# INPUT_OUTPUT.net
KiCad netlist of a schematic drawn in Altium Designer
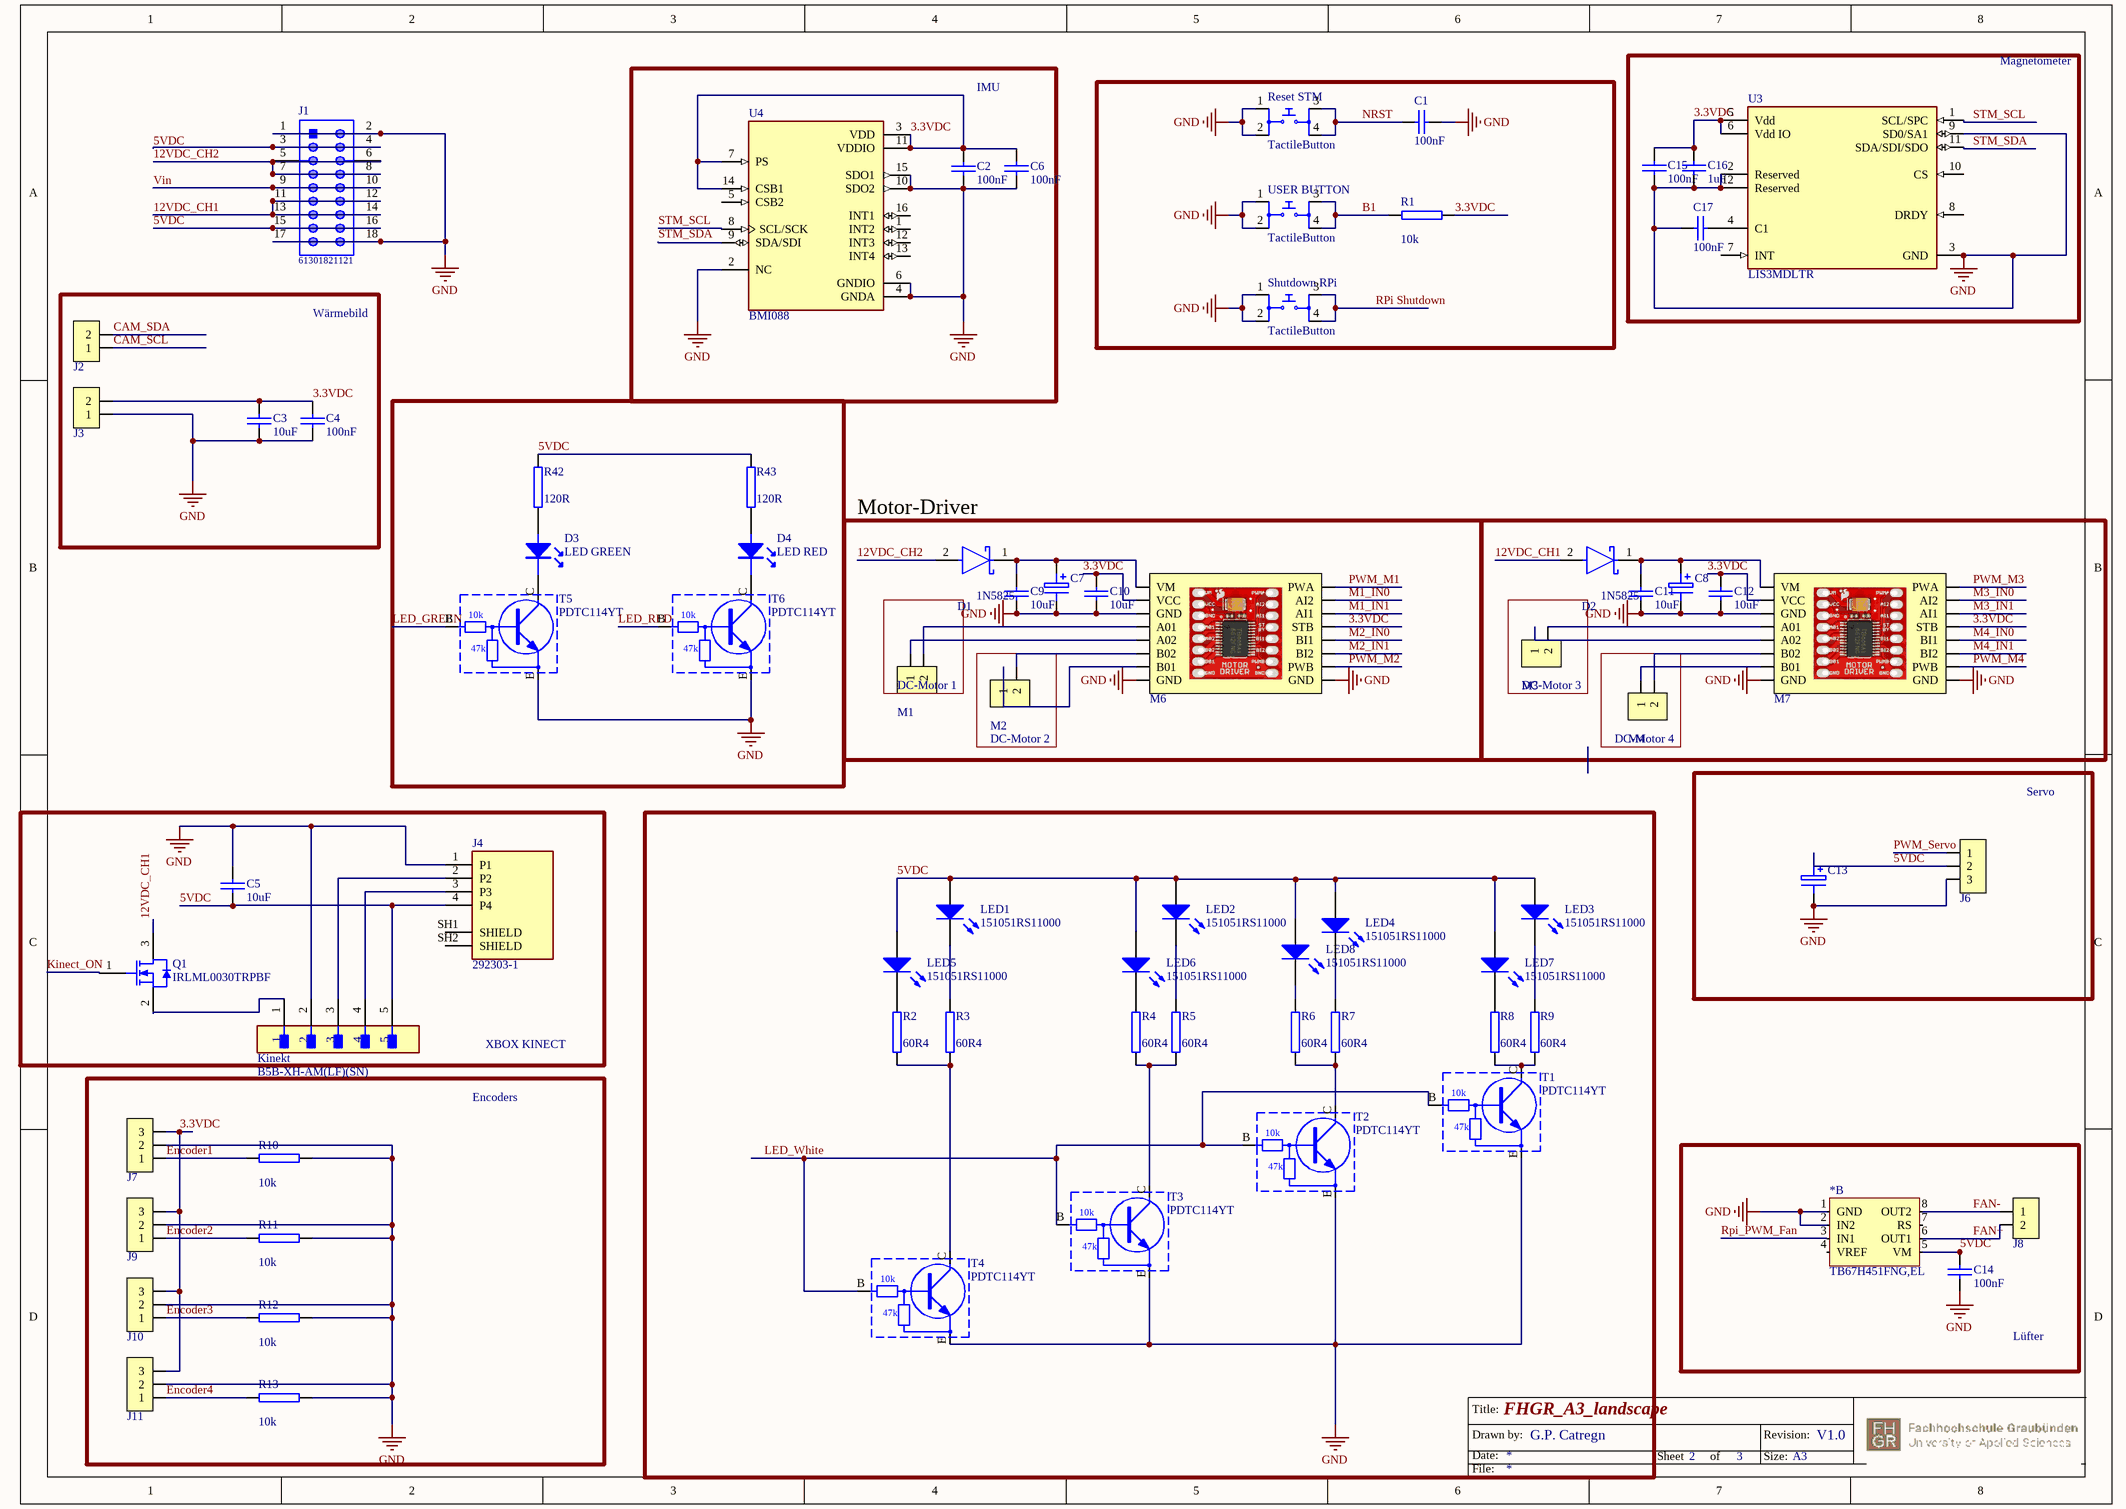
[diagram p0: INPUT_OUTPUT.SchDoc]

(export (version "E")
  (design (tool "Eeschema 10.0.6"))
  (components
    (comp (ref "*")
      (value "TB67H451FNG,EL")
      (footprint "SOIC127P600X170_HS-9N")
      (libsource (lib "TB67H451FNG,EL") (part "TB67H451FNG,EL"))
    )
    (comp (ref "C1")
      (value "100nF")
      (footprint "0603")
      (fields
        (field (name "TOLERANCE") "-20%/+80%")
        (field (name "VOLTAGE") "50V")
        (field (name "Comment") "C 100nF 0603")
      )
      (libsource (lib "FHGR_Altium_database") (part "Capacitor"))
    )
    (comp (ref "C2")
      (value "100nF")
      (footprint "0603")
      (fields
        (field (name "TOLERANCE") "-20%/+80%")
        (field (name "VOLTAGE") "50V")
        (field (name "Comment") "C 100nF 0603")
      )
      (libsource (lib "FHGR_Altium_database") (part "Capacitor"))
    )
    (comp (ref "C3")
      (value "10uF")
      (footprint "0603")
      (fields
        (field (name "TOLERANCE") "10%")
        (field (name "VOLTAGE") "16V")
        (field (name "Comment") "C 10uF 0603")
      )
      (libsource (lib "FHGR_Altium_database") (part "Capacitor"))
    )
    (comp (ref "C4")
      (value "100nF")
      (footprint "0603")
      (fields
        (field (name "TOLERANCE") "-20%/+80%")
        (field (name "VOLTAGE") "50V")
        (field (name "Comment") "C 100nF 0603")
      )
      (libsource (lib "FHGR_Altium_database") (part "Capacitor"))
    )
    (comp (ref "C5")
      (value "10uF")
      (footprint "0603")
      (fields
        (field (name "TOLERANCE") "10%")
        (field (name "VOLTAGE") "16V")
        (field (name "Comment") "C 10uF 0603")
      )
      (libsource (lib "FHGR_Altium_database") (part "Capacitor"))
    )
    (comp (ref "C6")
      (value "100nF")
      (footprint "0603")
      (fields
        (field (name "TOLERANCE") "-20%/+80%")
        (field (name "VOLTAGE") "50V")
        (field (name "Comment") "C 100nF 0603")
      )
      (libsource (lib "FHGR_Altium_database") (part "Capacitor"))
    )
    (comp (ref "C7")
      (value "C 100uF ALUM")
      (footprint "PCAP_8x10-ELEC00")
      (fields (field (name "TOLERANCE") "20%") (field (name "VOLTAGE") "50V"))
      (libsource (lib "FHGR_Altium_database") (part "Capacitor_Pol"))
    )
    (comp (ref "C8")
      (value "C 100uF ALUM")
      (footprint "PCAP_8x10-ELEC00")
      (fields (field (name "TOLERANCE") "20%") (field (name "VOLTAGE") "50V"))
      (libsource (lib "FHGR_Altium_database") (part "Capacitor_Pol"))
    )
    (comp (ref "C9")
      (value "10uF")
      (footprint "0603")
      (fields
        (field (name "TOLERANCE") "10%")
        (field (name "VOLTAGE") "16V")
        (field (name "Comment") "C 10uF 0603")
      )
      (libsource (lib "FHGR_Altium_database") (part "Capacitor"))
    )
    (comp (ref "C10")
      (value "10uF")
      (footprint "0603")
      (fields
        (field (name "TOLERANCE") "10%")
        (field (name "VOLTAGE") "16V")
        (field (name "Comment") "C 10uF 0603")
      )
      (libsource (lib "FHGR_Altium_database") (part "Capacitor"))
    )
    (comp (ref "C11")
      (value "10uF")
      (footprint "0603")
      (fields
        (field (name "TOLERANCE") "10%")
        (field (name "VOLTAGE") "16V")
        (field (name "Comment") "C 10uF 0603")
      )
      (libsource (lib "FHGR_Altium_database") (part "Capacitor"))
    )
    (comp (ref "C12")
      (value "10uF")
      (footprint "0603")
      (fields
        (field (name "TOLERANCE") "10%")
        (field (name "VOLTAGE") "16V")
        (field (name "Comment") "C 10uF 0603")
      )
      (libsource (lib "FHGR_Altium_database") (part "Capacitor"))
    )
    (comp (ref "C13")
      (value "C 100uF ALUM")
      (footprint "PCAP_8x10-ELEC00")
      (fields (field (name "TOLERANCE") "20%") (field (name "VOLTAGE") "50V"))
      (libsource (lib "FHGR_Altium_database") (part "Capacitor_Pol"))
    )
    (comp (ref "C14")
      (value "100nF")
      (footprint "0603")
      (fields
        (field (name "TOLERANCE") "-20%/+80%")
        (field (name "VOLTAGE") "50V")
        (field (name "Comment") "C 100nF 0603")
      )
      (libsource (lib "FHGR_Altium_database") (part "Capacitor"))
    )
    (comp (ref "C15")
      (value "100nF")
      (footprint "0603")
      (fields
        (field (name "TOLERANCE") "-20%/+80%")
        (field (name "VOLTAGE") "50V")
        (field (name "Comment") "C 100nF 0603")
      )
      (libsource (lib "FHGR_Altium_database") (part "Capacitor"))
    )
    (comp (ref "C16")
      (value "1uF")
      (footprint "0603")
      (fields
        (field (name "TOLERANCE") "10%")
        (field (name "VOLTAGE") "25V")
        (field (name "Comment") "C 1uF 0603")
      )
      (libsource (lib "FHGR_Altium_database") (part "Capacitor"))
    )
    (comp (ref "C17")
      (value "100nF")
      (footprint "0603")
      (fields
        (field (name "TOLERANCE") "-20%/+80%")
        (field (name "VOLTAGE") "50V")
        (field (name "Comment") "C 100nF 0603")
      )
      (libsource (lib "FHGR_Altium_database") (part "Capacitor"))
    )
    (comp (ref "D1")
      (value "1N5825")
      (footprint "Microsemi_1N5825_0")
      (libsource (lib "Diode_Microsemi_1N5825_eec") (part "1N5825"))
    )
    (comp (ref "D2")
      (value "1N5825")
      (footprint "Microsemi_1N5825_0")
      (libsource (lib "Diode_Microsemi_1N5825_eec") (part "1N5825"))
    )
    (comp (ref "D3")
      (value "LED GREEN")
      (footprint "LED_1206")
      (libsource (lib "FHGR_Altium_database") (part "LED"))
    )
    (comp (ref "D4")
      (value "LED RED")
      (footprint "LED_1206")
      (libsource (lib "FHGR_Altium_database") (part "LED"))
    )
    (comp (ref "J1")
      (value "61301821121")
      (footprint "61301821121")
      (description "THT Vertical Pin Header WR-PHD, Pitch 2.54 mm, Dual Row, 18 pins")
      (fields (field (name "MANUFACTURER") "Wurth Elektronik") (field (name "PUBLISHER") "WurthElektronik"))
      (libsource (lib "Altium Content Vault") (part "WE-CN-2P-M-R18"))
    )
    (comp (ref "J2")
      (value "2Pin_Male")
      (footprint "Header1x2_254")
      (libsource (lib "FHGR_Altium_database") (part "Connector2Pin"))
    )
    (comp (ref "J3")
      (value "2Pin_Male")
      (footprint "Header1x2_254")
      (libsource (lib "FHGR_Altium_database") (part "Connector2Pin"))
    )
    (comp (ref "J4")
      (value "292303-1")
      (footprint "TE_292303-1")
      (description "CONN USB RECEPT R/A TYPE A 4POS")
      (libsource (lib "292303-1") (part "292303-1"))
    )
    (comp (ref "J6")
      (value "3Pin_Male")
      (footprint "Header1x3_254")
      (libsource (lib "FHGR_Altium_database") (part "Connector3Pin"))
    )
    (comp (ref "J7")
      (value "3Pin_Male")
      (footprint "Header1x3_254")
      (libsource (lib "") (part "Connector3Pin_1"))
    )
    (comp (ref "J8")
      (value "2Pin_Male")
      (footprint "Header1x2_254")
      (libsource (lib "") (part "Connector2Pin_1"))
    )
    (comp (ref "J9")
      (value "3Pin_Male")
      (footprint "Header1x3_254")
      (libsource (lib "") (part "Connector3Pin_1"))
    )
    (comp (ref "J10")
      (value "3Pin_Male")
      (footprint "Header1x3_254")
      (libsource (lib "") (part "Connector3Pin_1"))
    )
    (comp (ref "J11")
      (value "3Pin_Male")
      (footprint "Header1x3_254")
      (libsource (lib "") (part "Connector3Pin_1"))
    )
    (comp (ref "Kinekt")
      (value "B5B-XH-AM(LF)(SN)")
      (footprint "FP-B5B-XH-AM_LF_SN-MFG")
      (description "CONN HEADER VERT 5POS 2.5MM")
      (libsource (lib "Altium Content Vault") (part "bf93c07fd2649a848d0ec8585582aab"))
    )
    (comp (ref "LED1")
      (value "151051RS11000")
      (footprint "Type 5mm")
      (description "THT LED round mono-color color lens, WL-TMRW, Red")
      (fields (field (name "MANUFACTURER") "Wuerth Elektronik"))
      (libsource (lib "Altium Content Vault") (part "WE-LED_K1A2-2"))
    )
    (comp (ref "LED2")
      (value "151051RS11000")
      (footprint "Type 5mm")
      (description "THT LED round mono-color color lens, WL-TMRW, Red")
      (fields (field (name "MANUFACTURER") "Wuerth Elektronik"))
      (libsource (lib "Altium Content Vault") (part "WE-LED_K1A2-2"))
    )
    (comp (ref "LED3")
      (value "151051RS11000")
      (footprint "Type 5mm")
      (description "THT LED round mono-color color lens, WL-TMRW, Red")
      (fields (field (name "MANUFACTURER") "Wuerth Elektronik"))
      (libsource (lib "Altium Content Vault") (part "WE-LED_K1A2-2"))
    )
    (comp (ref "LED4")
      (value "151051RS11000")
      (footprint "Type 5mm")
      (description "THT LED round mono-color color lens, WL-TMRW, Red")
      (fields (field (name "MANUFACTURER") "Wuerth Elektronik"))
      (libsource (lib "Altium Content Vault") (part "WE-LED_K1A2-2"))
    )
    (comp (ref "LED5")
      (value "151051RS11000")
      (footprint "Type 5mm")
      (description "THT LED round mono-color color lens, WL-TMRW, Red")
      (fields (field (name "MANUFACTURER") "Wuerth Elektronik"))
      (libsource (lib "Altium Content Vault") (part "WE-LED_K1A2-2"))
    )
    (comp (ref "LED6")
      (value "151051RS11000")
      (footprint "Type 5mm")
      (description "THT LED round mono-color color lens, WL-TMRW, Red")
      (fields (field (name "MANUFACTURER") "Wuerth Elektronik"))
      (libsource (lib "Altium Content Vault") (part "WE-LED_K1A2-2"))
    )
    (comp (ref "LED7")
      (value "151051RS11000")
      (footprint "Type 5mm")
      (description "THT LED round mono-color color lens, WL-TMRW, Red")
      (fields (field (name "MANUFACTURER") "Wuerth Elektronik"))
      (libsource (lib "Altium Content Vault") (part "WE-LED_K1A2-2"))
    )
    (comp (ref "LED8")
      (value "151051RS11000")
      (footprint "Type 5mm")
      (description "THT LED round mono-color color lens, WL-TMRW, Red")
      (fields (field (name "MANUFACTURER") "Wuerth Elektronik"))
      (libsource (lib "Altium Content Vault") (part "WE-LED_K1A2-2"))
    )
    (comp (ref "M1")
      (value "2Pin_Female")
      (footprint "OSTTE020104")
      (libsource (lib "FHGR_Altium_database") (part "Connector2Pin"))
    )
    (comp (ref "M2")
      (value "2Pin_Female")
      (footprint "OSTTE020104")
      (libsource (lib "FHGR_Altium_database") (part "Connector2Pin"))
    )
    (comp (ref "M3")
      (value "2Pin_Female")
      (footprint "OSTTE020104")
      (libsource (lib "FHGR_Altium_database") (part "Connector2Pin"))
    )
    (comp (ref "M4")
      (value "2Pin_Female")
      (footprint "OSTTE020104")
      (libsource (lib "FHGR_Altium_database") (part "Connector2Pin"))
    )
    (comp (ref "M6")
      (value "SPARKFUN_ROB_14451")
      (footprint "SPARKFUN_ROB_14451")
      (description "Dual Motor Driver")
      (libsource (lib "FHGR_Altium_database") (part "SPARKFUN_ROB_14451"))
    )
    (comp (ref "M7")
      (value "SPARKFUN_ROB_14451")
      (footprint "SPARKFUN_ROB_14451")
      (description "Dual Motor Driver")
      (libsource (lib "FHGR_Altium_database") (part "SPARKFUN_ROB_14451"))
    )
    (comp (ref "Q1")
      (value "IRLML0030TRPBF")
      (footprint "INTR-SOT-23-3_V")
      (description "HEXFET(R) Power MOSFET, 1.3 W, 4.4 ns, -55 to 150 degC, 3-Pin SOT-23, RoHS, Tape and Reel")
      (fields (field (name "MANUFACTURER") "International Rectifier"))
      (libsource (lib "Altium Content Vault") (part "NEMOS-GSD-3"))
    )
    (comp (ref "R1")
      (value "10k")
      (footprint "0805")
      (fields (field (name "TOLERANCE") "1%") (field (name "Comment") "R 10K 0805"))
      (libsource (lib "FHGR_Altium_database") (part "Resistor"))
    )
    (comp (ref "R2")
      (value "60R4")
      (footprint "0805")
      (fields (field (name "TOLERANCE") "1%") (field (name "Comment") "R 60R4 0805"))
      (libsource (lib "FHGR_Altium_database") (part "Resistor"))
    )
    (comp (ref "R3")
      (value "60R4")
      (footprint "0805")
      (fields (field (name "TOLERANCE") "1%") (field (name "Comment") "R 60R4 0805"))
      (libsource (lib "FHGR_Altium_database") (part "Resistor"))
    )
    (comp (ref "R4")
      (value "60R4")
      (footprint "0805")
      (fields (field (name "TOLERANCE") "1%") (field (name "Comment") "R 60R4 0805"))
      (libsource (lib "FHGR_Altium_database") (part "Resistor"))
    )
    (comp (ref "R5")
      (value "60R4")
      (footprint "0805")
      (fields (field (name "TOLERANCE") "1%") (field (name "Comment") "R 60R4 0805"))
      (libsource (lib "FHGR_Altium_database") (part "Resistor"))
    )
    (comp (ref "R6")
      (value "60R4")
      (footprint "0805")
      (fields (field (name "TOLERANCE") "1%") (field (name "Comment") "R 60R4 0805"))
      (libsource (lib "FHGR_Altium_database") (part "Resistor"))
    )
    (comp (ref "R7")
      (value "60R4")
      (footprint "0805")
      (fields (field (name "TOLERANCE") "1%") (field (name "Comment") "R 60R4 0805"))
      (libsource (lib "FHGR_Altium_database") (part "Resistor"))
    )
    (comp (ref "R8")
      (value "60R4")
      (footprint "0805")
      (fields (field (name "TOLERANCE") "1%") (field (name "Comment") "R 60R4 0805"))
      (libsource (lib "FHGR_Altium_database") (part "Resistor"))
    )
    (comp (ref "R9")
      (value "60R4")
      (footprint "0805")
      (fields (field (name "TOLERANCE") "1%") (field (name "Comment") "R 60R4 0805"))
      (libsource (lib "FHGR_Altium_database") (part "Resistor"))
    )
    (comp (ref "R10")
      (value "10k")
      (footprint "0805")
      (fields (field (name "TOLERANCE") "1%") (field (name "Comment") "R 10K 0805"))
      (libsource (lib "FHGR_Altium_database") (part "Resistor"))
    )
    (comp (ref "R11")
      (value "10k")
      (footprint "0805")
      (fields (field (name "TOLERANCE") "1%") (field (name "Comment") "R 10K 0805"))
      (libsource (lib "FHGR_Altium_database") (part "Resistor"))
    )
    (comp (ref "R12")
      (value "10k")
      (footprint "0805")
      (fields (field (name "TOLERANCE") "1%") (field (name "Comment") "R 10K 0805"))
      (libsource (lib "FHGR_Altium_database") (part "Resistor"))
    )
    (comp (ref "R13")
      (value "10k")
      (footprint "0805")
      (fields (field (name "TOLERANCE") "1%") (field (name "Comment") "R 10K 0805"))
      (libsource (lib "FHGR_Altium_database") (part "Resistor"))
    )
    (comp (ref "R42")
      (value "120R")
      (footprint "0805")
      (fields (field (name "TOLERANCE") "1%") (field (name "Comment") "R 120R 0805"))
      (libsource (lib "FHGR_Altium_database") (part "Resistor"))
    )
    (comp (ref "R43")
      (value "120R")
      (footprint "0805")
      (fields (field (name "TOLERANCE") "1%") (field (name "Comment") "R 120R 0805"))
      (libsource (lib "FHGR_Altium_database") (part "Resistor"))
    )
    (comp (ref "Reset STM")
      (value "TactileButton")
      (footprint "TactileButton-6x6mm")
      (fields (field (name "VOLTAGE") "12V"))
      (libsource (lib "FHGR_Altium_database") (part "Switch_Press_Button_4PIN"))
    )
    (comp (ref "Shutdown RPi")
      (value "TactileButton")
      (footprint "TactileButton-6x6mm")
      (fields (field (name "VOLTAGE") "12V"))
      (libsource (lib "FHGR_Altium_database") (part "Switch_Press_Button_4PIN"))
    )
    (comp (ref "T1")
      (value "PDTC114YT")
      (footprint "SOT-23")
      (fields (field (name "VOLTAGE") "50V"))
      (libsource (lib "FHGR_Altium_database") (part "NPN_10k_47k"))
    )
    (comp (ref "T2")
      (value "PDTC114YT")
      (footprint "SOT-23")
      (fields (field (name "VOLTAGE") "50V"))
      (libsource (lib "FHGR_Altium_database") (part "NPN_10k_47k"))
    )
    (comp (ref "T3")
      (value "PDTC114YT")
      (footprint "SOT-23")
      (fields (field (name "VOLTAGE") "50V"))
      (libsource (lib "FHGR_Altium_database") (part "NPN_10k_47k"))
    )
    (comp (ref "T4")
      (value "PDTC114YT")
      (footprint "SOT-23")
      (fields (field (name "VOLTAGE") "50V"))
      (libsource (lib "FHGR_Altium_database") (part "NPN_10k_47k"))
    )
    (comp (ref "T5")
      (value "PDTC114YT")
      (footprint "SOT-23")
      (fields (field (name "VOLTAGE") "50V"))
      (libsource (lib "FHGR_Altium_database") (part "NPN_10k_47k"))
    )
    (comp (ref "T6")
      (value "PDTC114YT")
      (footprint "SOT-23")
      (fields (field (name "VOLTAGE") "50V"))
      (libsource (lib "FHGR_Altium_database") (part "NPN_10k_47k"))
    )
    (comp (ref "U3")
      (value "LIS3MDLTR")
      (footprint "FP-VFLGA-12-8365767-MFG")
      (description "SENSOR MR I2C/SPI 12LGA")
      (fields
        (field (name "OCTOPART") "https://octopart.com/lis3mdltr-stmicroelectronics-29403125")
        (field (name "MANUFACTURER") "STMicroelectronics")
      )
      (libsource (lib "Altium Content Vault") (part "41c0331d4207a07573b21020ef49d7d"))
    )
    (comp (ref "U4")
      (value "BMI088")
      (footprint "PQFN50P450X300X100-16N")
      (libsource (lib "BMI088") (part "BMI088"))
    )
    (comp (ref "USER BUTTON")
      (value "TactileButton")
      (footprint "TactileButton-6x6mm")
      (fields (field (name "VOLTAGE") "12V"))
      (libsource (lib "FHGR_Altium_database") (part "Switch_Press_Button_4PIN"))
    )
  )
  (nets
    (net (code "1") (name "/3.3VDC") (class "Default")
      (node (ref "C10") (pin "1") (pintype "passive"))
      (node (ref "C12") (pin "1") (pintype "passive"))
      (node (ref "C15") (pin "1") (pintype "passive"))
      (node (ref "C16") (pin "1") (pintype "passive"))
      (node (ref "C2") (pin "1") (pintype "passive"))
      (node (ref "C3") (pin "1") (pintype "passive"))
      (node (ref "C4") (pin "1") (pintype "passive"))
      (node (ref "C6") (pin "1") (pintype "passive"))
      (node (ref "J10") (pin "3") (pinfunction "3_3") (pintype "passive"))
      (node (ref "J11") (pin "3") (pinfunction "3_3") (pintype "passive"))
      (node (ref "J3") (pin "2") (pinfunction "2_2") (pintype "passive"))
      (node (ref "J7") (pin "3") (pinfunction "3_3") (pintype "passive"))
      (node (ref "J9") (pin "3") (pinfunction "3_3") (pintype "passive"))
      (node (ref "M6") (pin "13") (pinfunction "STB_13") (pintype "passive"))
      (node (ref "M6") (pin "2") (pinfunction "VCC_2") (pintype "passive"))
      (node (ref "M7") (pin "13") (pinfunction "STB_13") (pintype "passive"))
      (node (ref "M7") (pin "2") (pinfunction "VCC_2") (pintype "passive"))
      (node (ref "R1") (pin "2") (pintype "passive"))
      (node (ref "U3") (pin "5") (pinfunction "Vdd_5") (pintype "power_in"))
      (node (ref "U3") (pin "6") (pinfunction "Vdd_IO_6") (pintype "power_in"))
      (node (ref "U4") (pin "11") (pinfunction "VDDIO_11") (pintype "power_in"))
      (node (ref "U4") (pin "14") (pinfunction "CSB1_14") (pintype "input"))
      (node (ref "U4") (pin "3") (pinfunction "VDD_3") (pintype "power_in"))
      (node (ref "U4") (pin "7") (pinfunction "PS_7") (pintype "input"))
    )
    (net (code "2") (name "/5VDC") (class "Default")
      (node (ref "*") (pin "5") (pinfunction "VM_5") (pintype "input"))
      (node (ref "C13") (pin "1") (pintype "passive"))
      (node (ref "C14") (pin "1") (pintype "passive"))
      (node (ref "C5") (pin "2") (pintype "passive"))
      (node (ref "J1") (pin "15") (pinfunction "15_15") (pintype "passive"))
      (node (ref "J1") (pin "16") (pinfunction "16_16") (pintype "passive"))
      (node (ref "J1") (pin "3") (pinfunction "3_3") (pintype "passive"))
      (node (ref "J1") (pin "4") (pinfunction "4_4") (pintype "passive"))
      (node (ref "J4") (pin "4") (pinfunction "P4_4") (pintype "passive"))
      (node (ref "J6") (pin "2") (pinfunction "2_2") (pintype "passive"))
      (node (ref "Kinekt") (pin "5") (pinfunction "5_5") (pintype "passive"))
      (node (ref "LED1") (pin "2") (pinfunction "A_2") (pintype "passive"))
      (node (ref "LED2") (pin "2") (pinfunction "A_2") (pintype "passive"))
      (node (ref "LED3") (pin "2") (pinfunction "A_2") (pintype "passive"))
      (node (ref "LED4") (pin "2") (pinfunction "A_2") (pintype "passive"))
      (node (ref "LED5") (pin "2") (pinfunction "A_2") (pintype "passive"))
      (node (ref "LED6") (pin "2") (pinfunction "A_2") (pintype "passive"))
      (node (ref "LED7") (pin "2") (pinfunction "A_2") (pintype "passive"))
      (node (ref "LED8") (pin "2") (pinfunction "A_2") (pintype "passive"))
      (node (ref "R42") (pin "2") (pintype "passive"))
      (node (ref "R43") (pin "2") (pintype "passive"))
    )
    (net (code "3") (name "/12VDC_CH1") (class "Default")
      (node (ref "D2") (pin "2") (pinfunction "A_2") (pintype "passive"))
      (node (ref "J1") (pin "11") (pinfunction "11_11") (pintype "passive"))
      (node (ref "J1") (pin "12") (pinfunction "12_12") (pintype "passive"))
      (node (ref "J1") (pin "13") (pinfunction "13_13") (pintype "passive"))
      (node (ref "J1") (pin "14") (pinfunction "14_14") (pintype "passive"))
      (node (ref "Q1") (pin "3") (pinfunction "D_3") (pintype "passive"))
    )
    (net (code "4") (name "/12VDC_CH2") (class "Default")
      (node (ref "D1") (pin "2") (pinfunction "A_2") (pintype "passive"))
      (node (ref "J1") (pin "5") (pinfunction "5_5") (pintype "passive"))
      (node (ref "J1") (pin "6") (pinfunction "6_6") (pintype "passive"))
      (node (ref "J1") (pin "7") (pinfunction "7_7") (pintype "passive"))
      (node (ref "J1") (pin "8") (pinfunction "8_8") (pintype "passive"))
    )
    (net (code "5") (name "/B1") (class "Default")
      (node (ref "R1") (pin "1") (pintype "passive"))
      (node (ref "USER BUTTON") (pin "3") (pintype "passive"))
      (node (ref "USER BUTTON") (pin "4") (pintype "passive"))
    )
    (net (code "6") (name "/CAM_SCL") (class "Default")
      (node (ref "J2") (pin "1") (pinfunction "1_1") (pintype "passive"))
    )
    (net (code "7") (name "/CAM_SDA") (class "Default")
      (node (ref "J2") (pin "2") (pinfunction "2_2") (pintype "passive"))
    )
    (net (code "8") (name "/Encoder1") (class "Default")
      (node (ref "J7") (pin "1") (pinfunction "1_1") (pintype "passive"))
      (node (ref "R10") (pin "1") (pintype "passive"))
    )
    (net (code "9") (name "/Encoder2") (class "Default")
      (node (ref "J9") (pin "1") (pinfunction "1_1") (pintype "passive"))
      (node (ref "R11") (pin "1") (pintype "passive"))
    )
    (net (code "10") (name "/Encoder3") (class "Default")
      (node (ref "J10") (pin "1") (pinfunction "1_1") (pintype "passive"))
      (node (ref "R12") (pin "2") (pintype "passive"))
    )
    (net (code "11") (name "/Encoder4") (class "Default")
      (node (ref "J11") (pin "1") (pinfunction "1_1") (pintype "passive"))
      (node (ref "R13") (pin "1") (pintype "passive"))
    )
    (net (code "12") (name "/FAN+") (class "Default")
      (node (ref "*") (pin "6") (pinfunction "OUT1_6") (pintype "input"))
      (node (ref "J8") (pin "2") (pinfunction "2_2") (pintype "passive"))
    )
    (net (code "13") (name "/FAN-") (class "Default")
      (node (ref "*") (pin "8") (pinfunction "OUT2_8") (pintype "input"))
      (node (ref "J8") (pin "1") (pinfunction "1_1") (pintype "passive"))
    )
    (net (code "14") (name "/Kinect_ON") (class "Default")
      (node (ref "Q1") (pin "1") (pinfunction "G_1") (pintype "passive"))
    )
    (net (code "15") (name "/LED_GREEN") (class "Default") (node (ref "T5") (pin "B") (pintype "passive")))
    (net (code "16") (name "/LED_RED") (class "Default") (node (ref "T6") (pin "B") (pintype "passive")))
    (net (code "17") (name "/LED_White") (class "Default")
      (node (ref "T1") (pin "B") (pintype "passive"))
      (node (ref "T2") (pin "B") (pintype "passive"))
      (node (ref "T3") (pin "B") (pintype "passive"))
      (node (ref "T4") (pin "B") (pintype "passive"))
    )
    (net (code "18") (name "/M1_IN0") (class "Default")
      (node (ref "M6") (pin "15") (pinfunction "AI2_15") (pintype "passive"))
    )
    (net (code "19") (name "/M1_IN1") (class "Default")
      (node (ref "M6") (pin "14") (pinfunction "AI1_14") (pintype "passive"))
    )
    (net (code "20") (name "/M2_IN0") (class "Default")
      (node (ref "M6") (pin "12") (pinfunction "BI1_12") (pintype "passive"))
    )
    (net (code "21") (name "/M2_IN1") (class "Default")
      (node (ref "M6") (pin "11") (pinfunction "BI2_11") (pintype "passive"))
    )
    (net (code "22") (name "/M3_IN0") (class "Default")
      (node (ref "M7") (pin "15") (pinfunction "AI2_15") (pintype "passive"))
    )
    (net (code "23") (name "/M3_IN1") (class "Default")
      (node (ref "M7") (pin "14") (pinfunction "AI1_14") (pintype "passive"))
    )
    (net (code "24") (name "/M4_IN0") (class "Default")
      (node (ref "M7") (pin "12") (pinfunction "BI1_12") (pintype "passive"))
    )
    (net (code "25") (name "/M4_IN1") (class "Default")
      (node (ref "M7") (pin "11") (pinfunction "BI2_11") (pintype "passive"))
    )
    (net (code "26") (name "/NRST") (class "Default")
      (node (ref "C1") (pin "1") (pintype "passive"))
      (node (ref "Reset STM") (pin "3") (pintype "passive"))
      (node (ref "Reset STM") (pin "4") (pintype "passive"))
    )
    (net (code "27") (name "/PWM_M1") (class "Default")
      (node (ref "M6") (pin "16") (pinfunction "PWA_16") (pintype "passive"))
    )
    (net (code "28") (name "/PWM_M2") (class "Default")
      (node (ref "M6") (pin "10") (pinfunction "PWB_10") (pintype "passive"))
    )
    (net (code "29") (name "/PWM_M3") (class "Default")
      (node (ref "M7") (pin "16") (pinfunction "PWA_16") (pintype "passive"))
    )
    (net (code "30") (name "/PWM_M4") (class "Default")
      (node (ref "M7") (pin "10") (pinfunction "PWB_10") (pintype "passive"))
    )
    (net (code "31") (name "/PWM_Servo") (class "Default")
      (node (ref "J6") (pin "1") (pinfunction "1_1") (pintype "passive"))
    )
    (net (code "32") (name "/RPi Shutdown") (class "Default")
      (node (ref "Shutdown RPi") (pin "3") (pintype "passive"))
      (node (ref "Shutdown RPi") (pin "4") (pintype "passive"))
    )
    (net (code "33") (name "/Rpi_PWM_Fan") (class "Default")
      (node (ref "*") (pin "3") (pinfunction "IN1_3") (pintype "input"))
    )
    (net (code "34") (name "/STM_SCL") (class "Default")
      (node (ref "U3") (pin "1") (pinfunction "SCL/SPC_1") (pintype "input"))
      (node (ref "U4") (pin "8") (pinfunction "SCL/SCK_8") (pintype "input"))
    )
    (net (code "35") (name "/STM_SDA") (class "Default")
      (node (ref "U3") (pin "11") (pinfunction "SDA/SDI/SDO_11") (pintype "bidirectional"))
      (node (ref "U4") (pin "9") (pinfunction "SDA/SDI_9") (pintype "bidirectional"))
    )
    (net (code "36") (name "/Vin") (class "Default")
      (node (ref "J1") (pin "10") (pinfunction "10_10") (pintype "passive"))
      (node (ref "J1") (pin "9") (pinfunction "9_9") (pintype "passive"))
    )
    (net (code "37") (name "GND") (class "Default")
      (node (ref "*") (pin "1") (pinfunction "GND_1") (pintype "input"))
      (node (ref "*") (pin "2") (pinfunction "IN2_2") (pintype "input"))
      (node (ref "C1") (pin "2") (pintype "passive"))
      (node (ref "C10") (pin "2") (pintype "passive"))
      (node (ref "C11") (pin "2") (pintype "passive"))
      (node (ref "C12") (pin "2") (pintype "passive"))
      (node (ref "C13") (pin "2") (pintype "passive"))
      (node (ref "C14") (pin "2") (pintype "passive"))
      (node (ref "C15") (pin "2") (pintype "passive"))
      (node (ref "C16") (pin "2") (pintype "passive"))
      (node (ref "C17") (pin "1") (pintype "passive"))
      (node (ref "C2") (pin "2") (pintype "passive"))
      (node (ref "C3") (pin "2") (pintype "passive"))
      (node (ref "C4") (pin "2") (pintype "passive"))
      (node (ref "C5") (pin "1") (pintype "passive"))
      (node (ref "C6") (pin "2") (pintype "passive"))
      (node (ref "C7") (pin "2") (pintype "passive"))
      (node (ref "C8") (pin "2") (pintype "passive"))
      (node (ref "C9") (pin "2") (pintype "passive"))
      (node (ref "J1") (pin "1") (pinfunction "1_1") (pintype "passive"))
      (node (ref "J1") (pin "17") (pinfunction "17_17") (pintype "passive"))
      (node (ref "J1") (pin "18") (pinfunction "18_18") (pintype "passive"))
      (node (ref "J1") (pin "2") (pinfunction "2_2") (pintype "passive"))
      (node (ref "J10") (pin "2") (pinfunction "2_2") (pintype "passive"))
      (node (ref "J11") (pin "2") (pinfunction "2_2") (pintype "passive"))
      (node (ref "J3") (pin "1") (pinfunction "1_1") (pintype "passive"))
      (node (ref "J4") (pin "1") (pinfunction "P1_1") (pintype "passive"))
      (node (ref "J6") (pin "3") (pinfunction "3_3") (pintype "passive"))
      (node (ref "J7") (pin "2") (pinfunction "2_2") (pintype "passive"))
      (node (ref "J9") (pin "2") (pinfunction "2_2") (pintype "passive"))
      (node (ref "Kinekt") (pin "2") (pinfunction "2_2") (pintype "passive"))
      (node (ref "M6") (pin "3") (pinfunction "GND_3") (pintype "passive"))
      (node (ref "M6") (pin "8") (pinfunction "GND_8") (pintype "passive"))
      (node (ref "M6") (pin "9") (pinfunction "GND_9") (pintype "passive"))
      (node (ref "M7") (pin "3") (pinfunction "GND_3") (pintype "passive"))
      (node (ref "M7") (pin "8") (pinfunction "GND_8") (pintype "passive"))
      (node (ref "M7") (pin "9") (pinfunction "GND_9") (pintype "passive"))
      (node (ref "R10") (pin "2") (pintype "passive"))
      (node (ref "R11") (pin "2") (pintype "passive"))
      (node (ref "R12") (pin "1") (pintype "passive"))
      (node (ref "R13") (pin "2") (pintype "passive"))
      (node (ref "Reset STM") (pin "1") (pintype "passive"))
      (node (ref "Reset STM") (pin "2") (pintype "passive"))
      (node (ref "Shutdown RPi") (pin "1") (pintype "passive"))
      (node (ref "Shutdown RPi") (pin "2") (pintype "passive"))
      (node (ref "T1") (pin "E") (pintype "passive"))
      (node (ref "T2") (pin "E") (pintype "passive"))
      (node (ref "T3") (pin "E") (pintype "passive"))
      (node (ref "T4") (pin "E") (pintype "passive"))
      (node (ref "T5") (pin "E") (pintype "passive"))
      (node (ref "T6") (pin "E") (pintype "passive"))
      (node (ref "U3") (pin "12") (pinfunction "Reserved_12") (pintype "passive"))
      (node (ref "U3") (pin "2") (pinfunction "Reserved_2") (pintype "passive"))
      (node (ref "U3") (pin "3") (pinfunction "GND_3") (pintype "power_in"))
      (node (ref "U3") (pin "9") (pinfunction "SD0/SA1_9") (pintype "bidirectional"))
      (node (ref "U4") (pin "10") (pinfunction "SDO2_10") (pintype "output"))
      (node (ref "U4") (pin "15") (pinfunction "SDO1_15") (pintype "output"))
      (node (ref "U4") (pin "2") (pinfunction "NC_2") (pintype "passive"))
      (node (ref "U4") (pin "4") (pinfunction "GNDA_4") (pintype "power_in"))
      (node (ref "U4") (pin "6") (pinfunction "GNDIO_6") (pintype "power_in"))
      (node (ref "USER BUTTON") (pin "1") (pintype "passive"))
      (node (ref "USER BUTTON") (pin "2") (pintype "passive"))
    )
    (net (code "38") (name "Net-(D1-C)") (class "Default")
      (node (ref "C7") (pin "1") (pintype "passive"))
      (node (ref "C9") (pin "1") (pintype "passive"))
      (node (ref "D1") (pin "1") (pinfunction "C_1") (pintype "passive"))
      (node (ref "M6") (pin "1") (pinfunction "VM_1") (pintype "passive"))
    )
    (net (code "39") (name "Net-(D2-C)") (class "Default")
      (node (ref "C11") (pin "1") (pintype "passive"))
      (node (ref "C8") (pin "1") (pintype "passive"))
      (node (ref "D2") (pin "1") (pinfunction "C_1") (pintype "passive"))
      (node (ref "M7") (pin "1") (pinfunction "VM_1") (pintype "passive"))
    )
    (net (code "40") (name "Net-(D3-PadA)") (class "Default")
      (node (ref "D3") (pin "A") (pintype "passive"))
      (node (ref "R42") (pin "1") (pintype "passive"))
    )
    (net (code "41") (name "Net-(D3-PadK)") (class "Default")
      (node (ref "D3") (pin "K") (pintype "passive"))
      (node (ref "T5") (pin "C") (pintype "passive"))
    )
    (net (code "42") (name "Net-(D4-PadA)") (class "Default")
      (node (ref "D4") (pin "A") (pintype "passive"))
      (node (ref "R43") (pin "1") (pintype "passive"))
    )
    (net (code "43") (name "Net-(D4-PadK)") (class "Default")
      (node (ref "D4") (pin "K") (pintype "passive"))
      (node (ref "T6") (pin "C") (pintype "passive"))
    )
    (net (code "44") (name "Net-(J4-P2)") (class "Default")
      (node (ref "J4") (pin "2") (pinfunction "P2_2") (pintype "passive"))
      (node (ref "Kinekt") (pin "3") (pinfunction "3_3") (pintype "passive"))
    )
    (net (code "45") (name "Net-(J4-P3)") (class "Default")
      (node (ref "J4") (pin "3") (pinfunction "P3_3") (pintype "passive"))
      (node (ref "Kinekt") (pin "4") (pinfunction "4_4") (pintype "passive"))
    )
    (net (code "46") (name "Net-(LED1-K)") (class "Default")
      (node (ref "LED1") (pin "1") (pinfunction "K_1") (pintype "passive"))
      (node (ref "R3") (pin "2") (pintype "passive"))
    )
    (net (code "47") (name "Net-(LED2-K)") (class "Default")
      (node (ref "LED2") (pin "1") (pinfunction "K_1") (pintype "passive"))
      (node (ref "R5") (pin "2") (pintype "passive"))
    )
    (net (code "48") (name "Net-(LED3-K)") (class "Default")
      (node (ref "LED3") (pin "1") (pinfunction "K_1") (pintype "passive"))
      (node (ref "R9") (pin "2") (pintype "passive"))
    )
    (net (code "49") (name "Net-(LED4-K)") (class "Default")
      (node (ref "LED4") (pin "1") (pinfunction "K_1") (pintype "passive"))
      (node (ref "R7") (pin "2") (pintype "passive"))
    )
    (net (code "50") (name "Net-(LED5-K)") (class "Default")
      (node (ref "LED5") (pin "1") (pinfunction "K_1") (pintype "passive"))
      (node (ref "R2") (pin "2") (pintype "passive"))
    )
    (net (code "51") (name "Net-(LED6-K)") (class "Default")
      (node (ref "LED6") (pin "1") (pinfunction "K_1") (pintype "passive"))
      (node (ref "R4") (pin "2") (pintype "passive"))
    )
    (net (code "52") (name "Net-(LED7-K)") (class "Default")
      (node (ref "LED7") (pin "1") (pinfunction "K_1") (pintype "passive"))
      (node (ref "R8") (pin "2") (pintype "passive"))
    )
    (net (code "53") (name "Net-(LED8-K)") (class "Default")
      (node (ref "LED8") (pin "1") (pinfunction "K_1") (pintype "passive"))
      (node (ref "R6") (pin "2") (pintype "passive"))
    )
    (net (code "54") (name "Net-(M6-A01)") (class "Default")
      (node (ref "M1") (pin "2") (pinfunction "2_2") (pintype "passive"))
      (node (ref "M6") (pin "4") (pinfunction "A01_4") (pintype "passive"))
    )
    (net (code "55") (name "Net-(M6-A02)") (class "Default")
      (node (ref "M1") (pin "1") (pinfunction "1_1") (pintype "passive"))
      (node (ref "M6") (pin "5") (pinfunction "A02_5") (pintype "passive"))
    )
    (net (code "56") (name "Net-(M6-B01)") (class "Default")
      (node (ref "M2") (pin "1") (pinfunction "1_1") (pintype "passive"))
      (node (ref "M6") (pin "7") (pinfunction "B01_7") (pintype "passive"))
    )
    (net (code "57") (name "Net-(M6-B02)") (class "Default")
      (node (ref "M2") (pin "2") (pinfunction "2_2") (pintype "passive"))
      (node (ref "M6") (pin "6") (pinfunction "B02_6") (pintype "passive"))
    )
    (net (code "58") (name "Net-(M7-A01)") (class "Default")
      (node (ref "M3") (pin "2") (pinfunction "2_2") (pintype "passive"))
      (node (ref "M7") (pin "4") (pinfunction "A01_4") (pintype "passive"))
    )
    (net (code "59") (name "Net-(M7-A02)") (class "Default")
      (node (ref "M3") (pin "1") (pinfunction "1_1") (pintype "passive"))
      (node (ref "M7") (pin "5") (pinfunction "A02_5") (pintype "passive"))
    )
    (net (code "60") (name "Net-(M7-B01)") (class "Default")
      (node (ref "M4") (pin "1") (pinfunction "1_1") (pintype "passive"))
      (node (ref "M7") (pin "7") (pinfunction "B01_7") (pintype "passive"))
    )
    (net (code "61") (name "Net-(M7-B02)") (class "Default")
      (node (ref "M4") (pin "2") (pinfunction "2_2") (pintype "passive"))
      (node (ref "M7") (pin "6") (pinfunction "B02_6") (pintype "passive"))
    )
    (net (code "62") (name "Net-(Q1-S)") (class "Default")
      (node (ref "Kinekt") (pin "1") (pinfunction "1_1") (pintype "passive"))
      (node (ref "Q1") (pin "2") (pinfunction "S_2") (pintype "passive"))
    )
    (net (code "63") (name "Net-(R2-Pad1)") (class "Default")
      (node (ref "R2") (pin "1") (pintype "passive"))
      (node (ref "R3") (pin "1") (pintype "passive"))
      (node (ref "T4") (pin "C") (pintype "passive"))
    )
    (net (code "64") (name "Net-(R4-Pad1)") (class "Default")
      (node (ref "R4") (pin "1") (pintype "passive"))
      (node (ref "R5") (pin "1") (pintype "passive"))
      (node (ref "T3") (pin "C") (pintype "passive"))
    )
    (net (code "65") (name "Net-(R6-Pad1)") (class "Default")
      (node (ref "R6") (pin "1") (pintype "passive"))
      (node (ref "R7") (pin "1") (pintype "passive"))
      (node (ref "T2") (pin "C") (pintype "passive"))
    )
    (net (code "66") (name "Net-(R8-Pad1)") (class "Default")
      (node (ref "R8") (pin "1") (pintype "passive"))
      (node (ref "R9") (pin "1") (pintype "passive"))
      (node (ref "T1") (pin "C") (pintype "passive"))
    )
    (net (code "67") (name "Net-(U3-C1)") (class "Default")
      (node (ref "C17") (pin "2") (pintype "passive"))
      (node (ref "U3") (pin "4") (pinfunction "C1_4") (pintype "passive"))
    )
    (net (code "68") (name "unconnected-(*B-RS-Pad7)") (class "Default")
      (node (ref "*") (pin "7") (pinfunction "RS_7") (pintype "input"))
    )
    (net (code "69") (name "unconnected-(*B-VREF-Pad4)") (class "Default")
      (node (ref "*") (pin "4") (pinfunction "VREF_4") (pintype "input"))
    )
    (net (code "70") (name "unconnected-(J4-SHIELD-PadSH1)") (class "Default")
      (node (ref "J4") (pin "SH1") (pinfunction "SHIELD_SH1") (pintype "passive"))
    )
    (net (code "71") (name "unconnected-(J4-SHIELD-PadSH2)") (class "Default")
      (node (ref "J4") (pin "SH2") (pinfunction "SHIELD_SH2") (pintype "passive"))
    )
    (net (code "72") (name "unconnected-(U3-CS-Pad10)") (class "Default")
      (node (ref "U3") (pin "10") (pinfunction "CS_10") (pintype "input"))
    )
    (net (code "73") (name "unconnected-(U3-DRDY-Pad8)") (class "Default")
      (node (ref "U3") (pin "8") (pinfunction "DRDY_8") (pintype "input"))
    )
    (net (code "74") (name "unconnected-(U3-INT-Pad7)") (class "Default")
      (node (ref "U3") (pin "7") (pinfunction "INT_7") (pintype "input"))
    )
    (net (code "75") (name "unconnected-(U4-CSB2-Pad5)") (class "Default")
      (node (ref "U4") (pin "5") (pinfunction "CSB2_5") (pintype "input"))
    )
    (net (code "76") (name "unconnected-(U4-INT1-Pad16)") (class "Default")
      (node (ref "U4") (pin "16") (pinfunction "INT1_16") (pintype "bidirectional"))
    )
    (net (code "77") (name "unconnected-(U4-INT2-Pad1)") (class "Default")
      (node (ref "U4") (pin "1") (pinfunction "INT2_1") (pintype "bidirectional"))
    )
    (net (code "78") (name "unconnected-(U4-INT3-Pad12)") (class "Default")
      (node (ref "U4") (pin "12") (pinfunction "INT3_12") (pintype "bidirectional"))
    )
    (net (code "79") (name "unconnected-(U4-INT4-Pad13)") (class "Default")
      (node (ref "U4") (pin "13") (pinfunction "INT4_13") (pintype "bidirectional"))
    )
  )
)
